# input2f.net
KiCad netlist of a schematic drawn in EAGLE
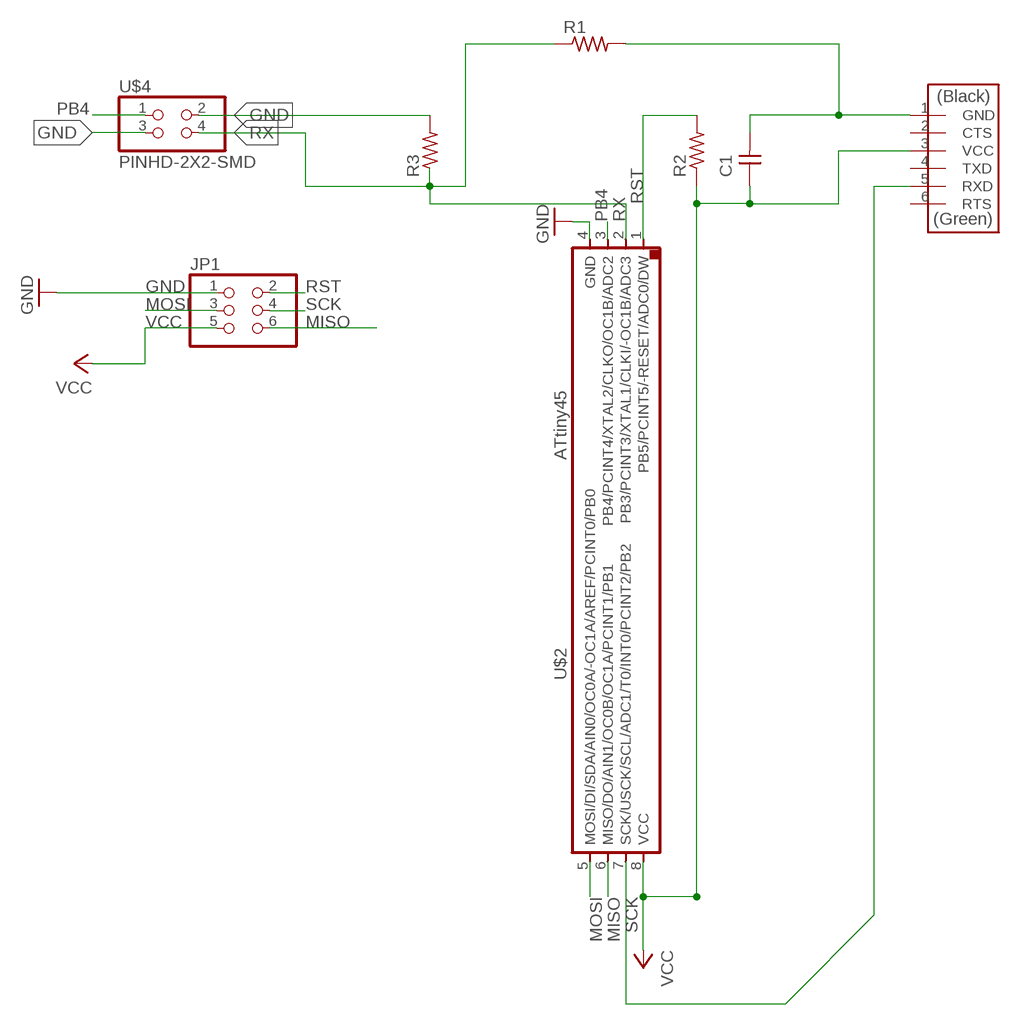
[diagram p0: schematic, sheet 1]

(export (version "E")
  (design (tool "Eeschema 10.0.6"))
  (components
    (comp (ref "C1")
      (value "CAP-UNPOLARIZEDFAB")
      (footprint "eagle-import:C1206FAB")
      (libsource (lib "eagle-import") (part "CAP-UNPOLARIZEDFAB"))
    )
    (comp (ref "JP1")
      (value "PINHD-2X3-SMD")
      (footprint "eagle-import:2X03SMD")
      (libsource (lib "eagle-import") (part "PINHD-2X3-SMD"))
    )
    (comp (ref "R1")
      (value "RES-US1206FAB")
      (footprint "eagle-import:R1206FAB")
      (libsource (lib "eagle-import") (part "RES-US1206FAB"))
    )
    (comp (ref "R2")
      (value "RES-US1206FAB")
      (footprint "eagle-import:R1206FAB")
      (libsource (lib "eagle-import") (part "RES-US1206FAB"))
    )
    (comp (ref "R3")
      (value "RES-US1206FAB")
      (footprint "eagle-import:R1206FAB")
      (libsource (lib "eagle-import") (part "RES-US1206FAB"))
    )
    (comp (ref "U$1")
      (value "FTDI-SMD-HEADER")
      (footprint "eagle-import:1X06SMD")
      (libsource (lib "eagle-import") (part "FTDI-SMD-HEADER"))
    )
    (comp (ref "U$2")
      (value "ATTINY45SI")
      (footprint "eagle-import:SOIC8")
      (libsource (lib "eagle-import") (part "ATTINY45SI"))
    )
    (comp (ref "U$4")
      (value "PINHD-2X2-SMD")
      (footprint "eagle-import:2X02SMD")
      (libsource (lib "eagle-import") (part "PINHD-2X2-SMD"))
    )
  )
  (nets
    (net (code "1") (name "/MISO") (class "Default")
      (node (ref "JP1") (pin "6") (pinfunction "6_6") (pintype "passive"))
      (node (ref "U$2") (pin "6") (pinfunction "MISO/DO/AIN1/OC0B/OC1A/PCINT1/PB1_6") (pintype "bidirectional"))
    )
    (net (code "2") (name "/MOSI") (class "Default")
      (node (ref "JP1") (pin "3") (pinfunction "3_3") (pintype "passive"))
      (node (ref "U$2") (pin "5") (pinfunction "MOSI/DI/SDA/AIN0/OC0A/-OC1A/AREF/PCINT0/PB0_5") (pintype "bidirectional"))
    )
    (net (code "3") (name "/PB4") (class "Default")
      (node (ref "U$2") (pin "3") (pinfunction "PB4/PCINT4/XTAL2/CLKO/OC1B/ADC2_3") (pintype "bidirectional"))
      (node (ref "U$4") (pin "1") (pinfunction "1_1") (pintype "passive"))
    )
    (net (code "4") (name "/RST") (class "Default")
      (node (ref "JP1") (pin "2") (pinfunction "2_2") (pintype "passive"))
      (node (ref "R2") (pin "2") (pinfunction "2_2") (pintype "passive"))
      (node (ref "U$2") (pin "1") (pinfunction "PB5/PCINT5/-RESET/ADC0/DW_1") (pintype "bidirectional"))
    )
    (net (code "5") (name "/SCK") (class "Default")
      (node (ref "JP1") (pin "4") (pinfunction "4_4") (pintype "passive"))
      (node (ref "U$1") (pin "5") (pinfunction "RXD_5") (pintype "bidirectional"))
      (node (ref "U$2") (pin "7") (pinfunction "SCK/USCK/SCL/ADC1/T0/INT0/PCINT2/PB2_7") (pintype "bidirectional"))
    )
    (net (code "6") (name "GND") (class "Default")
      (node (ref "JP1") (pin "1") (pinfunction "1_1") (pintype "passive"))
      (node (ref "R3") (pin "2") (pinfunction "2_2") (pintype "passive"))
      (node (ref "U$2") (pin "4") (pinfunction "GND_4") (pintype "bidirectional"))
      (node (ref "U$4") (pin "2") (pinfunction "2_2") (pintype "passive"))
      (node (ref "U$4") (pin "3") (pinfunction "3_3") (pintype "passive"))
    )
    (net (code "7") (name "Net-(U$1-GND)") (class "Default")
      (node (ref "C1") (pin "2") (pinfunction "2_2") (pintype "passive"))
      (node (ref "R1") (pin "2") (pinfunction "2_2") (pintype "passive"))
      (node (ref "U$1") (pin "1") (pinfunction "GND_1") (pintype "bidirectional"))
    )
    (net (code "8") (name "RX") (class "Default")
      (node (ref "R1") (pin "1") (pinfunction "1_1") (pintype "passive"))
      (node (ref "R3") (pin "1") (pinfunction "1_1") (pintype "passive"))
      (node (ref "U$2") (pin "2") (pinfunction "PB3/PCINT3/XTAL1/CLKI/-OC1B/ADC3_2") (pintype "bidirectional"))
      (node (ref "U$4") (pin "4") (pinfunction "4_4") (pintype "passive"))
    )
    (net (code "9") (name "VCC") (class "Default")
      (node (ref "C1") (pin "1") (pinfunction "1_1") (pintype "passive"))
      (node (ref "JP1") (pin "5") (pinfunction "5_5") (pintype "passive"))
      (node (ref "R2") (pin "1") (pinfunction "1_1") (pintype "passive"))
      (node (ref "U$1") (pin "3") (pinfunction "VCC_3") (pintype "bidirectional"))
      (node (ref "U$2") (pin "8") (pinfunction "VCC_8") (pintype "bidirectional"))
    )
    (net (code "10") (name "unconnected-(U$1-CTS-Pad2)") (class "Default")
      (node (ref "U$1") (pin "2") (pinfunction "CTS_2") (pintype "bidirectional"))
    )
    (net (code "11") (name "unconnected-(U$1-RTS-Pad6)") (class "Default")
      (node (ref "U$1") (pin "6") (pinfunction "RTS_6") (pintype "bidirectional"))
    )
    (net (code "12") (name "unconnected-(U$1-TXD-Pad4)") (class "Default")
      (node (ref "U$1") (pin "4") (pinfunction "TXD_4") (pintype "bidirectional"))
    )
  )
)
